# HackRPI-Badge.net
KiCad netlist of a schematic drawn in EAGLE
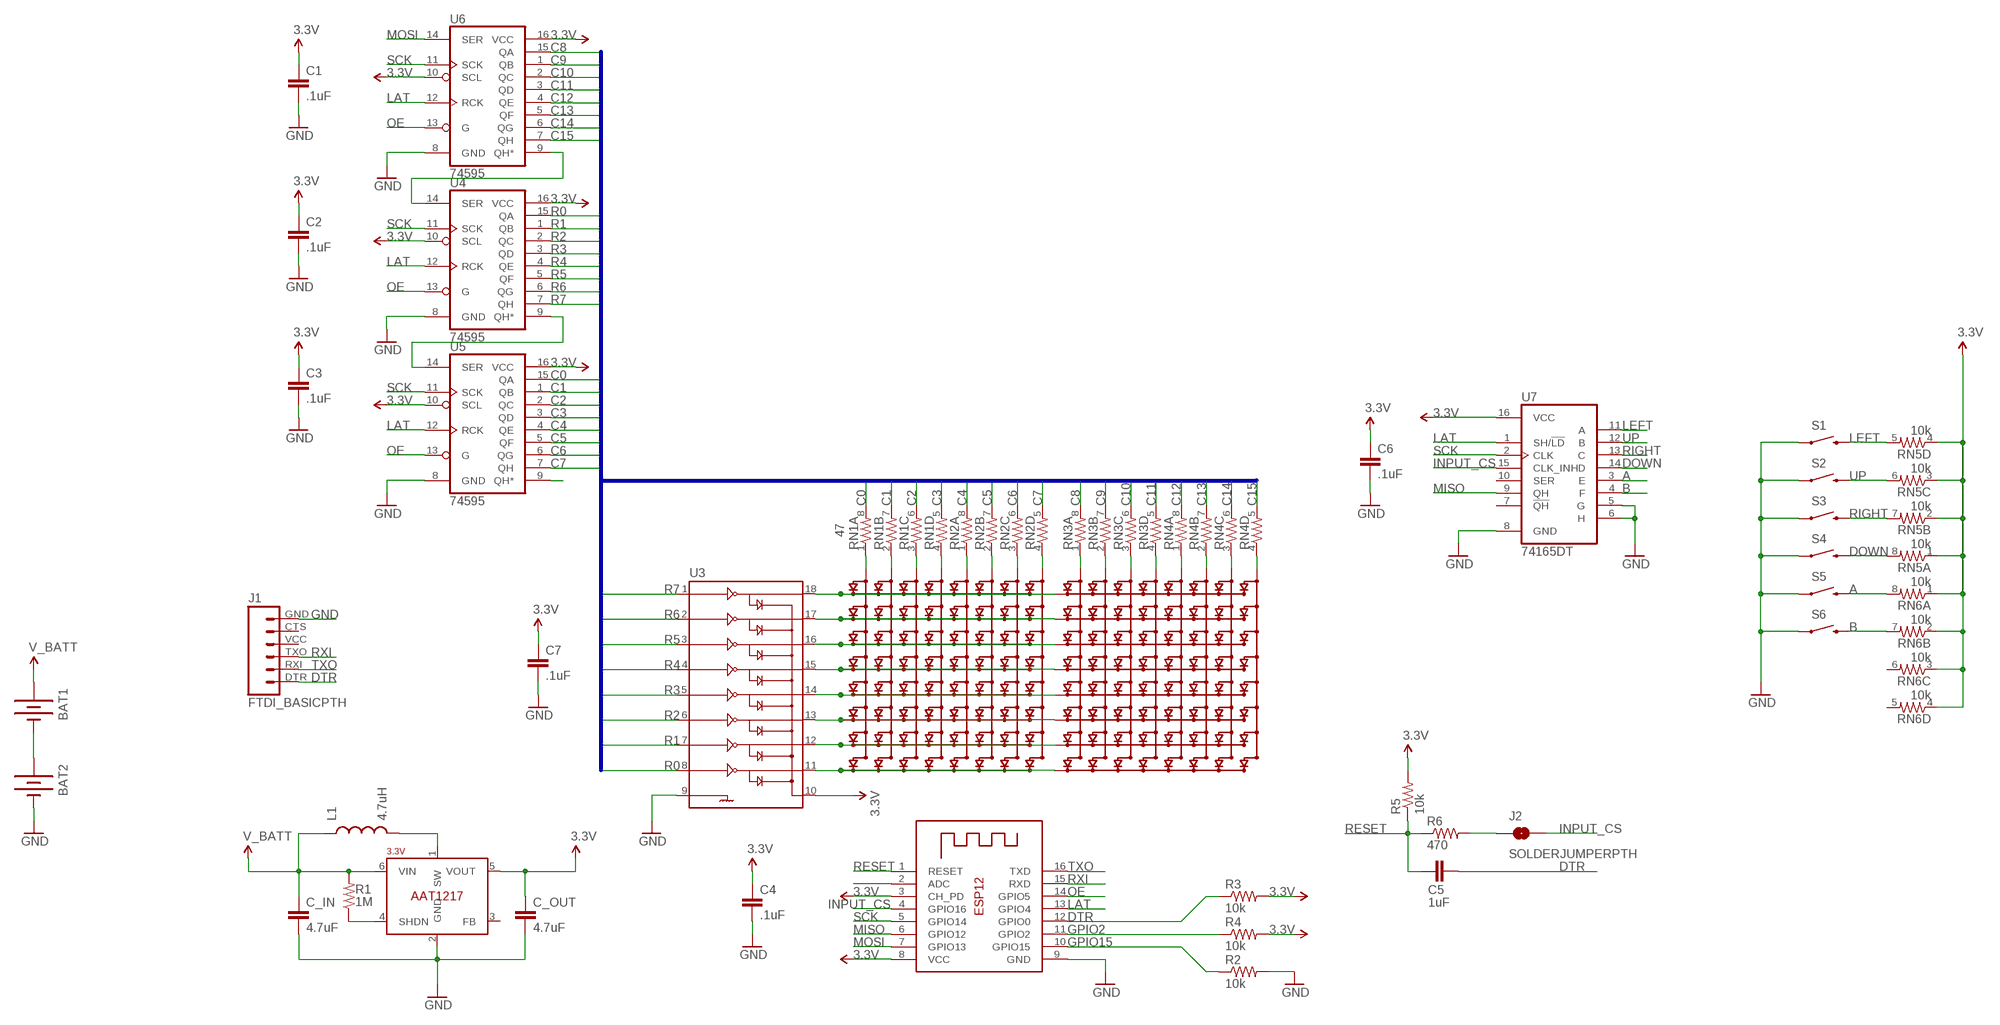
[diagram p0: schematic, sheet 1]

(export (version "E")
  (design (tool "Eeschema 10.0.6"))
  (components
    (comp (ref "BAT1")
      (value "BATTERYAAA")
      (footprint "eagle-import:BATTERY-AAA")
      (fields (field (name "PARTNO") "BK-82"))
      (libsource (lib "eagle-import") (part "BATTERYAAA"))
    )
    (comp (ref "BAT2")
      (value "BATTERYAAA")
      (footprint "eagle-import:BATTERY-AAA")
      (fields (field (name "PARTNO") "BK-82"))
      (libsource (lib "eagle-import") (part "BATTERYAAA"))
    )
    (comp (ref "C1")
      (value ".1uF")
      (footprint "eagle-import:0603-CAP")
      (fields (field (name "PARTNO") "CC0603ZRY5V9BB104"))
      (libsource (lib "eagle-import") (part "CAP0603-CAP"))
    )
    (comp (ref "C2")
      (value ".1uF")
      (footprint "eagle-import:0603-CAP")
      (fields (field (name "PARTNO") "CC0603ZRY5V9BB104"))
      (libsource (lib "eagle-import") (part "CAP0603-CAP"))
    )
    (comp (ref "C3")
      (value ".1uF")
      (footprint "eagle-import:0603-CAP")
      (fields (field (name "PARTNO") "CC0603ZRY5V9BB104"))
      (libsource (lib "eagle-import") (part "CAP0603-CAP"))
    )
    (comp (ref "C4")
      (value ".1uF")
      (footprint "eagle-import:0603-CAP")
      (fields (field (name "PARTNO") "CC0603ZRY5V9BB104"))
      (libsource (lib "eagle-import") (part "CAP0603-CAP"))
    )
    (comp (ref "C5")
      (value "1uF")
      (footprint "eagle-import:0603-CAP")
      (libsource (lib "eagle-import") (part "CAP0603-CAP"))
    )
    (comp (ref "C6")
      (value ".1uF")
      (footprint "eagle-import:0603-CAP")
      (fields (field (name "PARTNO") "CC0603ZRY5V9BB104"))
      (libsource (lib "eagle-import") (part "CAP0603-CAP"))
    )
    (comp (ref "C7")
      (value ".1uF")
      (footprint "eagle-import:0603-CAP")
      (fields (field (name "PARTNO") "CC0603ZRY5V9BB104"))
      (libsource (lib "eagle-import") (part "CAP0603-CAP"))
    )
    (comp (ref "C_IN")
      (value "4.7uF")
      (footprint "eagle-import:0805")
      (fields (field (name "PARTNO") "CL21A475KQFNNNG"))
      (libsource (lib "eagle-import") (part "CAP0805"))
    )
    (comp (ref "C_OUT")
      (value "4.7uF")
      (footprint "eagle-import:0805")
      (fields (field (name "PARTNO") "CL21A475KQFNNNG"))
      (libsource (lib "eagle-import") (part "CAP0805"))
    )
    (comp (ref "J1")
      (value "FTDI_BASICPTH")
      (footprint "eagle-import:FTDI_BASIC")
      (libsource (lib "eagle-import") (part "FTDI_BASICPTH"))
    )
    (comp (ref "J2")
      (value "SOLDERJUMPERPTH")
      (footprint "eagle-import:SJ_2S-PTH")
      (libsource (lib "eagle-import") (part "SOLDERJUMPERPTH"))
    )
    (comp (ref "L1")
      (value "4.7uH")
      (footprint "eagle-import:1007")
      (fields (field (name "PARTNO") "CIG22L4R7MNE"))
      (libsource (lib "eagle-import") (part "INDUCTOR1007"))
    )
    (comp (ref "LED_LEFT")
      (value "8X8LEDMATRIX_COLUMN_CATHODELDM-13488MI")
      (footprint "eagle-import:32MM_LEDMATRIX")
      (fields (field (name "PARTNO") "LDM-13488MI"))
      (libsource (lib "eagle-import") (part "8X8LEDMATRIX_COLUMN_CATHODELDM-13488MI"))
    )
    (comp (ref "LED_RIGHT")
      (value "8X8LEDMATRIX_COLUMN_CATHODELDM-13488MI")
      (footprint "eagle-import:32MM_LEDMATRIX")
      (fields (field (name "PARTNO") "LDM-13488MI"))
      (libsource (lib "eagle-import") (part "8X8LEDMATRIX_COLUMN_CATHODELDM-13488MI"))
    )
    (comp (ref "R1")
      (value "1M")
      (footprint "eagle-import:0603-RES")
      (fields (field (name "PARTNO") "RC0603JR-071ML"))
      (libsource (lib "eagle-import") (part "RESISTOR0603"))
    )
    (comp (ref "R2")
      (value "10k")
      (footprint "eagle-import:0603-RES")
      (fields (field (name "PARTNO") "RC0603JR-0710KL"))
      (libsource (lib "eagle-import") (part "RESISTOR0603"))
    )
    (comp (ref "R3")
      (value "10k")
      (footprint "eagle-import:0603-RES")
      (fields (field (name "PARTNO") "RC0603JR-0710KL"))
      (libsource (lib "eagle-import") (part "RESISTOR0603"))
    )
    (comp (ref "R4")
      (value "10k")
      (footprint "eagle-import:0603-RES")
      (fields (field (name "PARTNO") "RC0603JR-0710KL"))
      (libsource (lib "eagle-import") (part "RESISTOR0603"))
    )
    (comp (ref "R5")
      (value "10k")
      (footprint "eagle-import:0603-RES")
      (fields (field (name "PARTNO") "RC0603JR-0710KL"))
      (libsource (lib "eagle-import") (part "RESISTOR0603"))
    )
    (comp (ref "R6")
      (value "470")
      (footprint "eagle-import:0603-RES")
      (fields (field (name "PARTNO") "RC0603JR-07470RL"))
      (libsource (lib "eagle-import") (part "RESISTOR0603"))
    )
    (comp (ref "RN1")
      (value "47")
      (footprint "eagle-import:0603-ARV")
      (fields (field (name "PARTNO") "YC164-JR-0747RL"))
      (libsource (lib "eagle-import") (part "RESISTOR-ARRAY0603-ARV"))
    )
    (comp (ref "RN2")
      (value "47")
      (footprint "eagle-import:0603-ARV")
      (fields (field (name "PARTNO") "YC164-JR-0747RL"))
      (libsource (lib "eagle-import") (part "RESISTOR-ARRAY0603-ARV"))
    )
    (comp (ref "RN3")
      (value "47")
      (footprint "eagle-import:0603-ARV")
      (fields (field (name "PARTNO") "YC164-JR-0747RL"))
      (libsource (lib "eagle-import") (part "RESISTOR-ARRAY0603-ARV"))
    )
    (comp (ref "RN4")
      (value "47")
      (footprint "eagle-import:0603-ARV")
      (fields (field (name "PARTNO") "YC164-JR-0747RL"))
      (libsource (lib "eagle-import") (part "RESISTOR-ARRAY0603-ARV"))
    )
    (comp (ref "RN5")
      (value "10k")
      (footprint "eagle-import:0603-ARV")
      (fields (field (name "PARTNO") "742C083103JP"))
      (libsource (lib "eagle-import") (part "RESISTOR-ARRAY0603-ARV"))
    )
    (comp (ref "RN6")
      (value "10k")
      (footprint "eagle-import:0603-ARV")
      (fields (field (name "PARTNO") "742C083103JP"))
      (libsource (lib "eagle-import") (part "RESISTOR-ARRAY0603-ARV"))
    )
    (comp (ref "S1")
      (value "SWITCH-MOMENTARY-2PTH")
      (footprint "eagle-import:TACTILE-PTH")
      (fields (field (name "PARTNO") "1825910-6"))
      (libsource (lib "eagle-import") (part "SWITCH-MOMENTARY-2PTH"))
    )
    (comp (ref "S2")
      (value "SWITCH-MOMENTARY-2PTH")
      (footprint "eagle-import:TACTILE-PTH")
      (fields (field (name "PARTNO") "1825910-6"))
      (libsource (lib "eagle-import") (part "SWITCH-MOMENTARY-2PTH"))
    )
    (comp (ref "S3")
      (value "SWITCH-MOMENTARY-2PTH")
      (footprint "eagle-import:TACTILE-PTH")
      (fields (field (name "PARTNO") "1825910-6"))
      (libsource (lib "eagle-import") (part "SWITCH-MOMENTARY-2PTH"))
    )
    (comp (ref "S4")
      (value "SWITCH-MOMENTARY-2PTH")
      (footprint "eagle-import:TACTILE-PTH")
      (fields (field (name "PARTNO") "1825910-6"))
      (libsource (lib "eagle-import") (part "SWITCH-MOMENTARY-2PTH"))
    )
    (comp (ref "S5")
      (value "SWITCH-MOMENTARY-2PTH")
      (footprint "eagle-import:TACTILE-PTH")
      (fields (field (name "PARTNO") "1825910-6"))
      (libsource (lib "eagle-import") (part "SWITCH-MOMENTARY-2PTH"))
    )
    (comp (ref "S6")
      (value "SWITCH-MOMENTARY-2PTH")
      (footprint "eagle-import:TACTILE-PTH")
      (fields (field (name "PARTNO") "1825910-6"))
      (libsource (lib "eagle-import") (part "SWITCH-MOMENTARY-2PTH"))
    )
    (comp (ref "U1")
      (value "ESP-12")
      (footprint "eagle-import:ESP-12")
      (fields (field (name "PARTNO") "2491"))
      (libsource (lib "eagle-import") (part "ESP-12"))
    )
    (comp (ref "U2")
      (value "3.3V")
      (footprint "eagle-import:SOT23-6")
      (fields (field (name "PARTNO") "AAT1217ICA-3.3-T1"))
      (libsource (lib "eagle-import") (part "AAT1217"))
    )
    (comp (ref "U3")
      (value "ULN2803SOICW")
      (footprint "eagle-import:SO18L")
      (fields (field (name "PARTNO") "ULN2803AFWG,C,EL"))
      (libsource (lib "eagle-import") (part "ULN2803SOICW"))
    )
    (comp (ref "U4")
      (value "74595")
      (footprint "eagle-import:TSSOP16")
      (fields (field (name "PARTNO") "74HC595PW,118"))
      (libsource (lib "eagle-import") (part "74595"))
    )
    (comp (ref "U5")
      (value "74595")
      (footprint "eagle-import:TSSOP16")
      (fields (field (name "PARTNO") "74HC595PW,118"))
      (libsource (lib "eagle-import") (part "74595"))
    )
    (comp (ref "U6")
      (value "74595")
      (footprint "eagle-import:TSSOP16")
      (fields (field (name "PARTNO") "74HC595PW,118"))
      (libsource (lib "eagle-import") (part "74595"))
    )
    (comp (ref "U7")
      (value "74165DT")
      (footprint "eagle-import:TSSOP16")
      (fields (field (name "PARTNO") "MC74HC165ADTR2G"))
      (libsource (lib "eagle-import") (part "74165DT"))
    )
  )
  (nets
    (net (code "1") (name "/A") (class "Default")
      (node (ref "RN6") (pin "8") (pinfunction "2_8") (pintype "passive"))
      (node (ref "S5") (pin "3") (pinfunction "2_3") (pintype "passive"))
      (node (ref "U7") (pin "3") (pinfunction "E_3") (pintype "tri_state"))
    )
    (net (code "2") (name "/B") (class "Default")
      (node (ref "RN6") (pin "7") (pinfunction "2_7") (pintype "passive"))
      (node (ref "S6") (pin "3") (pinfunction "2_3") (pintype "passive"))
      (node (ref "U7") (pin "4") (pinfunction "F_4") (pintype "tri_state"))
    )
    (net (code "3") (name "/C0") (class "Default")
      (node (ref "RN1") (pin "8") (pinfunction "2_8") (pintype "passive"))
      (node (ref "U5") (pin "15") (pinfunction "QA_15") (pintype "tri_state"))
    )
    (net (code "4") (name "/C1") (class "Default")
      (node (ref "RN1") (pin "7") (pinfunction "2_7") (pintype "passive"))
      (node (ref "U5") (pin "1") (pinfunction "QB_1") (pintype "tri_state"))
    )
    (net (code "5") (name "/C2") (class "Default")
      (node (ref "RN1") (pin "6") (pinfunction "2_6") (pintype "passive"))
      (node (ref "U5") (pin "2") (pinfunction "QC_2") (pintype "tri_state"))
    )
    (net (code "6") (name "/C3") (class "Default")
      (node (ref "RN1") (pin "5") (pinfunction "2_5") (pintype "passive"))
      (node (ref "U5") (pin "3") (pinfunction "QD_3") (pintype "tri_state"))
    )
    (net (code "7") (name "/C4") (class "Default")
      (node (ref "RN2") (pin "8") (pinfunction "2_8") (pintype "passive"))
      (node (ref "U5") (pin "4") (pinfunction "QE_4") (pintype "tri_state"))
    )
    (net (code "8") (name "/C5") (class "Default")
      (node (ref "RN2") (pin "7") (pinfunction "2_7") (pintype "passive"))
      (node (ref "U5") (pin "5") (pinfunction "QF_5") (pintype "tri_state"))
    )
    (net (code "9") (name "/C6") (class "Default")
      (node (ref "RN2") (pin "6") (pinfunction "2_6") (pintype "passive"))
      (node (ref "U5") (pin "6") (pinfunction "QG_6") (pintype "tri_state"))
    )
    (net (code "10") (name "/C7") (class "Default")
      (node (ref "RN2") (pin "5") (pinfunction "2_5") (pintype "passive"))
      (node (ref "U5") (pin "7") (pinfunction "QH_7") (pintype "tri_state"))
    )
    (net (code "11") (name "/C8") (class "Default")
      (node (ref "RN3") (pin "8") (pinfunction "2_8") (pintype "passive"))
      (node (ref "U6") (pin "15") (pinfunction "QA_15") (pintype "tri_state"))
    )
    (net (code "12") (name "/C9") (class "Default")
      (node (ref "RN3") (pin "7") (pinfunction "2_7") (pintype "passive"))
      (node (ref "U6") (pin "1") (pinfunction "QB_1") (pintype "tri_state"))
    )
    (net (code "13") (name "/C10") (class "Default")
      (node (ref "RN3") (pin "6") (pinfunction "2_6") (pintype "passive"))
      (node (ref "U6") (pin "2") (pinfunction "QC_2") (pintype "tri_state"))
    )
    (net (code "14") (name "/C11") (class "Default")
      (node (ref "RN3") (pin "5") (pinfunction "2_5") (pintype "passive"))
      (node (ref "U6") (pin "3") (pinfunction "QD_3") (pintype "tri_state"))
    )
    (net (code "15") (name "/C12") (class "Default")
      (node (ref "RN4") (pin "8") (pinfunction "2_8") (pintype "passive"))
      (node (ref "U6") (pin "4") (pinfunction "QE_4") (pintype "tri_state"))
    )
    (net (code "16") (name "/C13") (class "Default")
      (node (ref "RN4") (pin "7") (pinfunction "2_7") (pintype "passive"))
      (node (ref "U6") (pin "5") (pinfunction "QF_5") (pintype "tri_state"))
    )
    (net (code "17") (name "/C14") (class "Default")
      (node (ref "RN4") (pin "6") (pinfunction "2_6") (pintype "passive"))
      (node (ref "U6") (pin "6") (pinfunction "QG_6") (pintype "tri_state"))
    )
    (net (code "18") (name "/C15") (class "Default")
      (node (ref "RN4") (pin "5") (pinfunction "2_5") (pintype "passive"))
      (node (ref "U6") (pin "7") (pinfunction "QH_7") (pintype "tri_state"))
    )
    (net (code "19") (name "/DOWN") (class "Default")
      (node (ref "RN5") (pin "8") (pinfunction "2_8") (pintype "passive"))
      (node (ref "S4") (pin "3") (pinfunction "2_3") (pintype "passive"))
      (node (ref "U7") (pin "14") (pinfunction "D_14") (pintype "tri_state"))
    )
    (net (code "20") (name "/DTR") (class "Default")
      (node (ref "C5") (pin "2") (pinfunction "2_2") (pintype "passive"))
      (node (ref "J1") (pin "DTR") (pinfunction "1_DTR") (pintype "passive"))
      (node (ref "R3") (pin "1") (pinfunction "1_1") (pintype "passive"))
      (node (ref "U1") (pin "12") (pinfunction "GPIO0_12") (pintype "bidirectional"))
    )
    (net (code "21") (name "/GPIO2") (class "Default")
      (node (ref "R4") (pin "1") (pinfunction "1_1") (pintype "passive"))
      (node (ref "U1") (pin "11") (pinfunction "GPIO2_11") (pintype "bidirectional"))
    )
    (net (code "22") (name "/GPIO15") (class "Default")
      (node (ref "R2") (pin "1") (pinfunction "1_1") (pintype "passive"))
      (node (ref "U1") (pin "10") (pinfunction "GPIO15_10") (pintype "bidirectional"))
    )
    (net (code "23") (name "/INPUT_CS") (class "Default")
      (node (ref "J2") (pin "2") (pinfunction "2_2") (pintype "passive"))
      (node (ref "U1") (pin "4") (pinfunction "GPIO16_4") (pintype "bidirectional"))
      (node (ref "U7") (pin "15") (pinfunction "CLK_INH_15") (pintype "input"))
    )
    (net (code "24") (name "/LAT") (class "Default")
      (node (ref "U1") (pin "13") (pinfunction "GPIO4_13") (pintype "bidirectional"))
      (node (ref "U4") (pin "12") (pinfunction "RCK_12") (pintype "input"))
      (node (ref "U5") (pin "12") (pinfunction "RCK_12") (pintype "input"))
      (node (ref "U6") (pin "12") (pinfunction "RCK_12") (pintype "input"))
      (node (ref "U7") (pin "1") (pinfunction "SH/~{LD}_1") (pintype "input"))
    )
    (net (code "25") (name "/LEFT") (class "Default")
      (node (ref "RN5") (pin "5") (pinfunction "2_5") (pintype "passive"))
      (node (ref "S1") (pin "3") (pinfunction "2_3") (pintype "passive"))
      (node (ref "U7") (pin "11") (pinfunction "A_11") (pintype "tri_state"))
    )
    (net (code "26") (name "/MISO") (class "Default")
      (node (ref "U1") (pin "6") (pinfunction "GPIO12_6") (pintype "bidirectional"))
      (node (ref "U7") (pin "9") (pinfunction "QH_9") (pintype "tri_state"))
    )
    (net (code "27") (name "/MOSI") (class "Default")
      (node (ref "U1") (pin "7") (pinfunction "GPIO13_7") (pintype "bidirectional"))
      (node (ref "U6") (pin "14") (pinfunction "SER_14") (pintype "input"))
    )
    (net (code "28") (name "/OE") (class "Default")
      (node (ref "U1") (pin "14") (pinfunction "GPIO5_14") (pintype "bidirectional"))
      (node (ref "U4") (pin "13") (pinfunction "G_13") (pintype "input"))
      (node (ref "U5") (pin "13") (pinfunction "G_13") (pintype "input"))
      (node (ref "U6") (pin "13") (pinfunction "G_13") (pintype "input"))
    )
    (net (code "29") (name "/R0") (class "Default")
      (node (ref "U3") (pin "8") (pinfunction "8_8") (pintype "bidirectional"))
      (node (ref "U4") (pin "15") (pinfunction "QA_15") (pintype "tri_state"))
    )
    (net (code "30") (name "/R1") (class "Default")
      (node (ref "U3") (pin "7") (pinfunction "7_7") (pintype "bidirectional"))
      (node (ref "U4") (pin "1") (pinfunction "QB_1") (pintype "tri_state"))
    )
    (net (code "31") (name "/R2") (class "Default")
      (node (ref "U3") (pin "6") (pinfunction "6_6") (pintype "bidirectional"))
      (node (ref "U4") (pin "2") (pinfunction "QC_2") (pintype "tri_state"))
    )
    (net (code "32") (name "/R3") (class "Default")
      (node (ref "U3") (pin "5") (pinfunction "5_5") (pintype "bidirectional"))
      (node (ref "U4") (pin "3") (pinfunction "QD_3") (pintype "tri_state"))
    )
    (net (code "33") (name "/R4") (class "Default")
      (node (ref "U3") (pin "4") (pinfunction "4_4") (pintype "bidirectional"))
      (node (ref "U4") (pin "4") (pinfunction "QE_4") (pintype "tri_state"))
    )
    (net (code "34") (name "/R5") (class "Default")
      (node (ref "U3") (pin "3") (pinfunction "3_3") (pintype "bidirectional"))
      (node (ref "U4") (pin "5") (pinfunction "QF_5") (pintype "tri_state"))
    )
    (net (code "35") (name "/R6") (class "Default")
      (node (ref "U3") (pin "2") (pinfunction "2_2") (pintype "bidirectional"))
      (node (ref "U4") (pin "6") (pinfunction "QG_6") (pintype "tri_state"))
    )
    (net (code "36") (name "/R7") (class "Default")
      (node (ref "U3") (pin "1") (pinfunction "1_1") (pintype "bidirectional"))
      (node (ref "U4") (pin "7") (pinfunction "QH_7") (pintype "tri_state"))
    )
    (net (code "37") (name "/RESET") (class "Default")
      (node (ref "C5") (pin "1") (pinfunction "1_1") (pintype "passive"))
      (node (ref "R5") (pin "1") (pinfunction "1_1") (pintype "passive"))
      (node (ref "R6") (pin "1") (pinfunction "1_1") (pintype "passive"))
      (node (ref "U1") (pin "1") (pinfunction "RESET_1") (pintype "input"))
    )
    (net (code "38") (name "/RIGHT") (class "Default")
      (node (ref "RN5") (pin "7") (pinfunction "2_7") (pintype "passive"))
      (node (ref "S3") (pin "3") (pinfunction "2_3") (pintype "passive"))
      (node (ref "U7") (pin "13") (pinfunction "C_13") (pintype "tri_state"))
    )
    (net (code "39") (name "/RXI") (class "Default")
      (node (ref "J1") (pin "TXO") (pinfunction "3_TXO") (pintype "passive"))
      (node (ref "U1") (pin "15") (pinfunction "RXD_15") (pintype "input"))
    )
    (net (code "40") (name "/SCK") (class "Default")
      (node (ref "U1") (pin "5") (pinfunction "GPIO14_5") (pintype "bidirectional"))
      (node (ref "U4") (pin "11") (pinfunction "SCK_11") (pintype "input"))
      (node (ref "U5") (pin "11") (pinfunction "SCK_11") (pintype "input"))
      (node (ref "U6") (pin "11") (pinfunction "SCK_11") (pintype "input"))
      (node (ref "U7") (pin "2") (pinfunction "CLK_2") (pintype "input"))
    )
    (net (code "41") (name "/TXO") (class "Default")
      (node (ref "J1") (pin "RXI") (pinfunction "2_RXI") (pintype "passive"))
      (node (ref "U1") (pin "16") (pinfunction "TXD_16") (pintype "output"))
    )
    (net (code "42") (name "/UP") (class "Default")
      (node (ref "RN5") (pin "6") (pinfunction "2_6") (pintype "passive"))
      (node (ref "S2") (pin "3") (pinfunction "2_3") (pintype "passive"))
      (node (ref "U7") (pin "12") (pinfunction "B_12") (pintype "tri_state"))
    )
    (net (code "43") (name "3.3V") (class "Default")
      (node (ref "C1") (pin "1") (pinfunction "1_1") (pintype "passive"))
      (node (ref "C2") (pin "1") (pinfunction "1_1") (pintype "passive"))
      (node (ref "C3") (pin "1") (pinfunction "1_1") (pintype "passive"))
      (node (ref "C4") (pin "1") (pinfunction "1_1") (pintype "passive"))
      (node (ref "C6") (pin "1") (pinfunction "1_1") (pintype "passive"))
      (node (ref "C7") (pin "1") (pinfunction "1_1") (pintype "passive"))
      (node (ref "C_OUT") (pin "1") (pinfunction "1_1") (pintype "passive"))
      (node (ref "R3") (pin "2") (pinfunction "2_2") (pintype "passive"))
      (node (ref "R4") (pin "2") (pinfunction "2_2") (pintype "passive"))
      (node (ref "R5") (pin "2") (pinfunction "2_2") (pintype "passive"))
      (node (ref "RN5") (pin "1") (pinfunction "1_1") (pintype "passive"))
      (node (ref "RN5") (pin "2") (pinfunction "1_2") (pintype "passive"))
      (node (ref "RN5") (pin "3") (pinfunction "1_3") (pintype "passive"))
      (node (ref "RN5") (pin "4") (pinfunction "1_4") (pintype "passive"))
      (node (ref "RN6") (pin "1") (pinfunction "1_1") (pintype "passive"))
      (node (ref "RN6") (pin "2") (pinfunction "1_2") (pintype "passive"))
      (node (ref "RN6") (pin "3") (pinfunction "1_3") (pintype "passive"))
      (node (ref "RN6") (pin "4") (pinfunction "1_4") (pintype "passive"))
      (node (ref "U1") (pin "3") (pinfunction "CH_PD_3") (pintype "input"))
      (node (ref "U1") (pin "8") (pinfunction "VCC_8") (pintype "power_in"))
      (node (ref "U2") (pin "5") (pinfunction "VOUT_5") (pintype "power_in"))
      (node (ref "U3") (pin "10") (pinfunction "10_10") (pintype "bidirectional"))
      (node (ref "U4") (pin "10") (pinfunction "SCL_10") (pintype "input"))
      (node (ref "U4") (pin "16") (pinfunction "VCC_16") (pintype "power_in"))
      (node (ref "U5") (pin "10") (pinfunction "SCL_10") (pintype "input"))
      (node (ref "U5") (pin "16") (pinfunction "VCC_16") (pintype "power_in"))
      (node (ref "U6") (pin "10") (pinfunction "SCL_10") (pintype "input"))
      (node (ref "U6") (pin "16") (pinfunction "VCC_16") (pintype "power_in"))
      (node (ref "U7") (pin "16") (pinfunction "VCC_16") (pintype "power_in"))
    )
    (net (code "44") (name "GND") (class "Default")
      (node (ref "BAT2") (pin "GND@1") (pinfunction "-_GND@1") (pintype "power_in"))
      (node (ref "C1") (pin "2") (pinfunction "2_2") (pintype "passive"))
      (node (ref "C2") (pin "2") (pinfunction "2_2") (pintype "passive"))
      (node (ref "C3") (pin "2") (pinfunction "2_2") (pintype "passive"))
      (node (ref "C4") (pin "2") (pinfunction "2_2") (pintype "passive"))
      (node (ref "C6") (pin "2") (pinfunction "2_2") (pintype "passive"))
      (node (ref "C7") (pin "2") (pinfunction "2_2") (pintype "passive"))
      (node (ref "C_IN") (pin "2") (pinfunction "2_2") (pintype "passive"))
      (node (ref "C_OUT") (pin "2") (pinfunction "2_2") (pintype "passive"))
      (node (ref "J1") (pin "GND") (pinfunction "6_GND") (pintype "passive"))
      (node (ref "R2") (pin "2") (pinfunction "2_2") (pintype "passive"))
      (node (ref "S1") (pin "1") (pinfunction "1_1") (pintype "passive"))
      (node (ref "S2") (pin "1") (pinfunction "1_1") (pintype "passive"))
      (node (ref "S3") (pin "1") (pinfunction "1_1") (pintype "passive"))
      (node (ref "S4") (pin "1") (pinfunction "1_1") (pintype "passive"))
      (node (ref "S5") (pin "1") (pinfunction "1_1") (pintype "passive"))
      (node (ref "S6") (pin "1") (pinfunction "1_1") (pintype "passive"))
      (node (ref "U1") (pin "9") (pinfunction "GND_9") (pintype "power_in"))
      (node (ref "U2") (pin "2") (pinfunction "GND_2") (pintype "power_in"))
      (node (ref "U3") (pin "9") (pinfunction "9_9") (pintype "bidirectional"))
      (node (ref "U4") (pin "8") (pinfunction "GND_8") (pintype "power_in"))
      (node (ref "U5") (pin "8") (pinfunction "GND_8") (pintype "power_in"))
      (node (ref "U6") (pin "8") (pinfunction "GND_8") (pintype "power_in"))
      (node (ref "U7") (pin "5") (pinfunction "G_5") (pintype "tri_state"))
      (node (ref "U7") (pin "6") (pinfunction "H_6") (pintype "tri_state"))
      (node (ref "U7") (pin "8") (pinfunction "GND_8") (pintype "power_in"))
    )
    (net (code "45") (name "Net-(BAT1--)") (class "Default")
      (node (ref "BAT1") (pin "GND@1") (pinfunction "-_GND@1") (pintype "power_in"))
      (node (ref "BAT2") (pin "PWR@1") (pinfunction "+_PWR@1") (pintype "power_in"))
    )
    (net (code "46") (name "Net-(J2-Pad1)") (class "Default")
      (node (ref "J2") (pin "1") (pinfunction "1_1") (pintype "passive"))
      (node (ref "R6") (pin "2") (pinfunction "2_2") (pintype "passive"))
    )
    (net (code "47") (name "Net-(LED_LEFT-C1)") (class "Default")
      (node (ref "LED_LEFT") (pin "13") (pinfunction "C1_13") (pintype "bidirectional"))
      (node (ref "RN1") (pin "1") (pinfunction "1_1") (pintype "passive"))
    )
    (net (code "48") (name "Net-(LED_LEFT-C2)") (class "Default")
      (node (ref "LED_LEFT") (pin "3") (pinfunction "C2_3") (pintype "bidirectional"))
      (node (ref "RN1") (pin "2") (pinfunction "1_2") (pintype "passive"))
    )
    (net (code "49") (name "Net-(LED_LEFT-C3)") (class "Default")
      (node (ref "LED_LEFT") (pin "4") (pinfunction "C3_4") (pintype "bidirectional"))
      (node (ref "RN1") (pin "3") (pinfunction "1_3") (pintype "passive"))
    )
    (net (code "50") (name "Net-(LED_LEFT-C4)") (class "Default")
      (node (ref "LED_LEFT") (pin "10") (pinfunction "C4_10") (pintype "bidirectional"))
      (node (ref "RN1") (pin "4") (pinfunction "1_4") (pintype "passive"))
    )
    (net (code "51") (name "Net-(LED_LEFT-C5)") (class "Default")
      (node (ref "LED_LEFT") (pin "6") (pinfunction "C5_6") (pintype "bidirectional"))
      (node (ref "RN2") (pin "1") (pinfunction "1_1") (pintype "passive"))
    )
    (net (code "52") (name "Net-(LED_LEFT-C6)") (class "Default")
      (node (ref "LED_LEFT") (pin "11") (pinfunction "C6_11") (pintype "bidirectional"))
      (node (ref "RN2") (pin "2") (pinfunction "1_2") (pintype "passive"))
    )
    (net (code "53") (name "Net-(LED_LEFT-C7)") (class "Default")
      (node (ref "LED_LEFT") (pin "15") (pinfunction "C7_15") (pintype "bidirectional"))
      (node (ref "RN2") (pin "3") (pinfunction "1_3") (pintype "passive"))
    )
    (net (code "54") (name "Net-(LED_LEFT-C8)") (class "Default")
      (node (ref "LED_LEFT") (pin "16") (pinfunction "C8_16") (pintype "bidirectional"))
      (node (ref "RN2") (pin "4") (pinfunction "1_4") (pintype "passive"))
    )
    (net (code "55") (name "Net-(LED_LEFT-R1)") (class "Default")
      (node (ref "LED_LEFT") (pin "9") (pinfunction "R1_9") (pintype "bidirectional"))
      (node (ref "LED_RIGHT") (pin "9") (pinfunction "R1_9") (pintype "bidirectional"))
      (node (ref "U3") (pin "18") (pinfunction "18_18") (pintype "bidirectional"))
    )
    (net (code "56") (name "Net-(LED_LEFT-R2)") (class "Default")
      (node (ref "LED_LEFT") (pin "14") (pinfunction "R2_14") (pintype "bidirectional"))
      (node (ref "LED_RIGHT") (pin "14") (pinfunction "R2_14") (pintype "bidirectional"))
      (node (ref "U3") (pin "17") (pinfunction "17_17") (pintype "bidirectional"))
    )
    (net (code "57") (name "Net-(LED_LEFT-R3)") (class "Default")
      (node (ref "LED_LEFT") (pin "8") (pinfunction "R3_8") (pintype "bidirectional"))
      (node (ref "LED_RIGHT") (pin "8") (pinfunction "R3_8") (pintype "bidirectional"))
      (node (ref "U3") (pin "16") (pinfunction "16_16") (pintype "bidirectional"))
    )
    (net (code "58") (name "Net-(LED_LEFT-R4)") (class "Default")
      (node (ref "LED_LEFT") (pin "12") (pinfunction "R4_12") (pintype "bidirectional"))
      (node (ref "LED_RIGHT") (pin "12") (pinfunction "R4_12") (pintype "bidirectional"))
      (node (ref "U3") (pin "15") (pinfunction "15_15") (pintype "bidirectional"))
    )
    (net (code "59") (name "Net-(LED_LEFT-R5)") (class "Default")
      (node (ref "LED_LEFT") (pin "1") (pinfunction "R5_1") (pintype "bidirectional"))
      (node (ref "LED_RIGHT") (pin "1") (pinfunction "R5_1") (pintype "bidirectional"))
      (node (ref "U3") (pin "14") (pinfunction "14_14") (pintype "bidirectional"))
    )
    (net (code "60") (name "Net-(LED_LEFT-R6)") (class "Default")
      (node (ref "LED_LEFT") (pin "7") (pinfunction "R6_7") (pintype "bidirectional"))
      (node (ref "LED_RIGHT") (pin "7") (pinfunction "R6_7") (pintype "bidirectional"))
      (node (ref "U3") (pin "13") (pinfunction "13_13") (pintype "bidirectional"))
    )
    (net (code "61") (name "Net-(LED_LEFT-R7)") (class "Default")
      (node (ref "LED_LEFT") (pin "2") (pinfunction "R7_2") (pintype "bidirectional"))
      (node (ref "LED_RIGHT") (pin "2") (pinfunction "R7_2") (pintype "bidirectional"))
      (node (ref "U3") (pin "12") (pinfunction "12_12") (pintype "bidirectional"))
    )
    (net (code "62") (name "Net-(LED_LEFT-R8)") (class "Default")
      (node (ref "LED_LEFT") (pin "5") (pinfunction "R8_5") (pintype "bidirectional"))
      (node (ref "LED_RIGHT") (pin "5") (pinfunction "R8_5") (pintype "bidirectional"))
      (node (ref "U3") (pin "11") (pinfunction "11_11") (pintype "bidirectional"))
    )
    (net (code "63") (name "Net-(LED_RIGHT-C1)") (class "Default")
      (node (ref "LED_RIGHT") (pin "13") (pinfunction "C1_13") (pintype "bidirectional"))
      (node (ref "RN3") (pin "1") (pinfunction "1_1") (pintype "passive"))
    )
    (net (code "64") (name "Net-(LED_RIGHT-C2)") (class "Default")
      (node (ref "LED_RIGHT") (pin "3") (pinfunction "C2_3") (pintype "bidirectional"))
      (node (ref "RN3") (pin "2") (pinfunction "1_2") (pintype "passive"))
    )
    (net (code "65") (name "Net-(LED_RIGHT-C3)") (class "Default")
      (node (ref "LED_RIGHT") (pin "4") (pinfunction "C3_4") (pintype "bidirectional"))
      (node (ref "RN3") (pin "3") (pinfunction "1_3") (pintype "passive"))
    )
    (net (code "66") (name "Net-(LED_RIGHT-C4)") (class "Default")
      (node (ref "LED_RIGHT") (pin "10") (pinfunction "C4_10") (pintype "bidirectional"))
      (node (ref "RN3") (pin "4") (pinfunction "1_4") (pintype "passive"))
    )
    (net (code "67") (name "Net-(LED_RIGHT-C5)") (class "Default")
      (node (ref "LED_RIGHT") (pin "6") (pinfunction "C5_6") (pintype "bidirectional"))
      (node (ref "RN4") (pin "1") (pinfunction "1_1") (pintype "passive"))
    )
    (net (code "68") (name "Net-(LED_RIGHT-C6)") (class "Default")
      (node (ref "LED_RIGHT") (pin "11") (pinfunction "C6_11") (pintype "bidirectional"))
      (node (ref "RN4") (pin "2") (pinfunction "1_2") (pintype "passive"))
    )
    (net (code "69") (name "Net-(LED_RIGHT-C7)") (class "Default")
      (node (ref "LED_RIGHT") (pin "15") (pinfunction "C7_15") (pintype "bidirectional"))
      (node (ref "RN4") (pin "3") (pinfunction "1_3") (pintype "passive"))
    )
    (net (code "70") (name "Net-(LED_RIGHT-C8)") (class "Default")
      (node (ref "LED_RIGHT") (pin "16") (pinfunction "C8_16") (pintype "bidirectional"))
      (node (ref "RN4") (pin "4") (pinfunction "1_4") (pintype "passive"))
    )
    (net (code "71") (name "Net-(U2-SHDN)") (class "Default")
      (node (ref "R1") (pin "1") (pinfunction "1_1") (pintype "passive"))
      (node (ref "U2") (pin "4") (pinfunction "SHDN_4") (pintype "input"))
    )
    (net (code "72") (name "Net-(U2-SW)") (class "Default")
      (node (ref "L1") (pin "2") (pinfunction "2_2") (pintype "passive"))
      (node (ref "U2") (pin "1") (pinfunction "SW_1") (pintype "input"))
    )
    (net (code "73") (name "Net-(U4-QH*)") (class "Default")
      (node (ref "U4") (pin "9") (pinfunction "QH*_9") (pintype "tri_state"))
      (node (ref "U5") (pin "14") (pinfunction "SER_14") (pintype "input"))
    )
    (net (code "74") (name "Net-(U4-SER)") (class "Default")
      (node (ref "U4") (pin "14") (pinfunction "SER_14") (pintype "input"))
      (node (ref "U6") (pin "9") (pinfunction "QH*_9") (pintype "tri_state"))
    )
    (net (code "75") (name "V_BATT") (class "Default")
      (node (ref "BAT1") (pin "PWR@1") (pinfunction "+_PWR@1") (pintype "power_in"))
      (node (ref "C_IN") (pin "1") (pinfunction "1_1") (pintype "passive"))
      (node (ref "L1") (pin "1") (pinfunction "1_1") (pintype "passive"))
      (node (ref "R1") (pin "2") (pinfunction "2_2") (pintype "passive"))
      (node (ref "U2") (pin "6") (pinfunction "VIN_6") (pintype "power_in"))
    )
    (net (code "76") (name "unconnected-(J1-4-PadVCC)") (class "Default")
      (node (ref "J1") (pin "VCC") (pinfunction "4_VCC") (pintype "passive"))
    )
    (net (code "77") (name "unconnected-(J1-5-PadCTS)") (class "Default")
      (node (ref "J1") (pin "CTS") (pinfunction "5_CTS") (pintype "passive"))
    )
    (net (code "78") (name "unconnected-(RN6C-2-Pad6)") (class "Default")
      (node (ref "RN6") (pin "6") (pinfunction "2_6") (pintype "passive"))
    )
    (net (code "79") (name "unconnected-(RN6D-2-Pad5)") (class "Default")
      (node (ref "RN6") (pin "5") (pinfunction "2_5") (pintype "passive"))
    )
    (net (code "80") (name "unconnected-(U1-ADC-Pad2)") (class "Default")
      (node (ref "U1") (pin "2") (pinfunction "ADC_2") (pintype "passive"))
    )
    (net (code "81") (name "unconnected-(U2-FB-Pad3)") (class "Default")
      (node (ref "U2") (pin "3") (pinfunction "FB_3") (pintype "input"))
    )
    (net (code "82") (name "unconnected-(U5-QH*-Pad9)") (class "Default")
      (node (ref "U5") (pin "9") (pinfunction "QH*_9") (pintype "tri_state"))
    )
    (net (code "83") (name "unconnected-(U7-SER-Pad10)") (class "Default")
      (node (ref "U7") (pin "10") (pinfunction "SER_10") (pintype "input"))
    )
    (net (code "84") (name "unconnected-(U7-~{QH}-Pad7)") (class "Default")
      (node (ref "U7") (pin "7") (pinfunction "~{QH}_7") (pintype "input"))
    )
  )
)
